# base_board.net
KiCad netlist of a schematic drawn in EAGLE
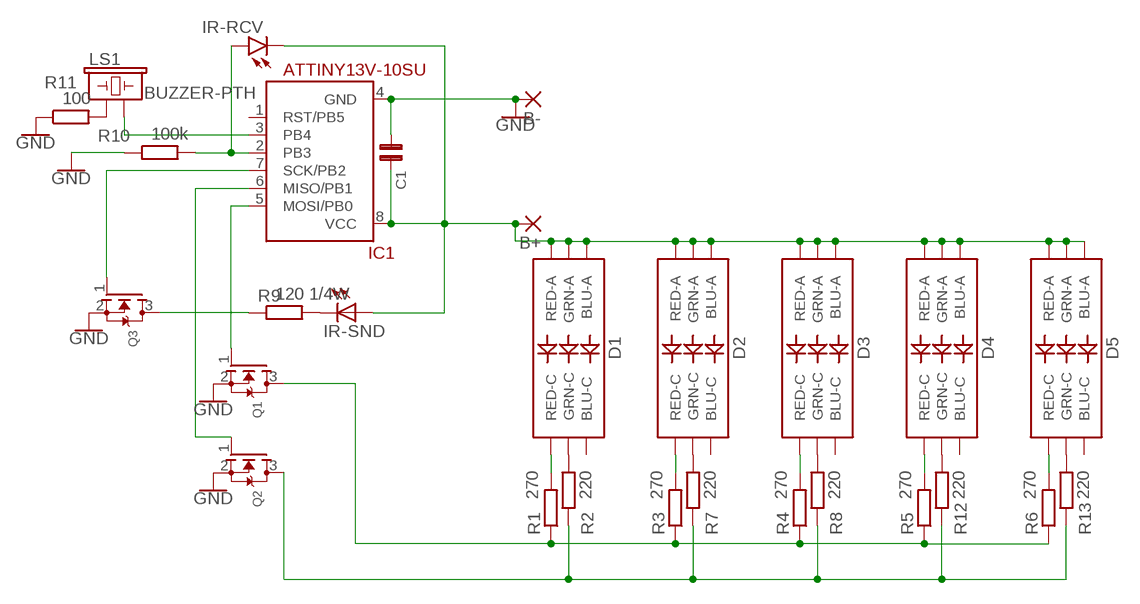
[diagram p0: schematic, sheet 1]

(export (version "E")
  (design (tool "Eeschema 10.0.6"))
  (components
    (comp (ref "B+")
      (value "2,15/1,0")
      (footprint "eagle-import:2,15_1,0")
      (libsource (lib "eagle-import") (part "2,15/1,0"))
    )
    (comp (ref "B-")
      (value "2,15/1,0")
      (footprint "eagle-import:2,15_1,0")
      (libsource (lib "eagle-import") (part "2,15/1,0"))
    )
    (comp (ref "C1")
      (value "C0805")
      (footprint "eagle-import:0805")
      (libsource (lib "eagle-import") (part "C0805"))
    )
    (comp (ref "D1")
      (value "LED-RGBNO_IC")
      (footprint "eagle-import:LED-TRICOLOR-5050")
      (libsource (lib "eagle-import") (part "LED-RGBNO_IC"))
    )
    (comp (ref "D2")
      (value "LED-RGBNO_IC")
      (footprint "eagle-import:LED-TRICOLOR-5050")
      (libsource (lib "eagle-import") (part "LED-RGBNO_IC"))
    )
    (comp (ref "D3")
      (value "LED-RGBNO_IC")
      (footprint "eagle-import:LED-TRICOLOR-5050")
      (libsource (lib "eagle-import") (part "LED-RGBNO_IC"))
    )
    (comp (ref "D4")
      (value "LED-RGBNO_IC")
      (footprint "eagle-import:LED-TRICOLOR-5050")
      (libsource (lib "eagle-import") (part "LED-RGBNO_IC"))
    )
    (comp (ref "D5")
      (value "LED-RGBNO_IC")
      (footprint "eagle-import:LED-TRICOLOR-5050")
      (libsource (lib "eagle-import") (part "LED-RGBNO_IC"))
    )
    (comp (ref "IC1")
      (value "ATTINY13V-10SU")
      (footprint "eagle-import:SOIC8")
      (libsource (lib "eagle-import") (part "ATTINY13V-10SU"))
    )
    (comp (ref "IR-RCV")
      (value "LED_INPUT")
      (footprint "eagle-import:LED3MM")
      (libsource (lib "eagle-import") (part "LED_INPUT"))
    )
    (comp (ref "IR-SND")
      (value "LED3MM")
      (footprint "eagle-import:LED3MM")
      (libsource (lib "eagle-import") (part "LED3MM"))
    )
    (comp (ref "LS1")
      (value "BUZZER-PTH")
      (footprint "eagle-import:BUZZER-12MM")
      (libsource (lib "eagle-import") (part "BUZZER-PTH"))
    )
    (comp (ref "Q1")
      (value "MOSFET-NREFLOW")
      (footprint "eagle-import:SOT23")
      (libsource (lib "eagle-import") (part "MOSFET-NREFLOW"))
    )
    (comp (ref "Q2")
      (value "MOSFET-NREFLOW")
      (footprint "eagle-import:SOT23")
      (libsource (lib "eagle-import") (part "MOSFET-NREFLOW"))
    )
    (comp (ref "Q3")
      (value "MOSFET-NREFLOW")
      (footprint "eagle-import:SOT23")
      (libsource (lib "eagle-import") (part "MOSFET-NREFLOW"))
    )
    (comp (ref "R1")
      (value "270")
      (footprint "eagle-import:R2012")
      (libsource (lib "eagle-import") (part "R-EU_R2012"))
    )
    (comp (ref "R2")
      (value "220")
      (footprint "eagle-import:R2012")
      (libsource (lib "eagle-import") (part "R-EU_R2012"))
    )
    (comp (ref "R3")
      (value "270")
      (footprint "eagle-import:R2012")
      (libsource (lib "eagle-import") (part "R-EU_R2012"))
    )
    (comp (ref "R4")
      (value "270")
      (footprint "eagle-import:R2012")
      (libsource (lib "eagle-import") (part "R-EU_R2012"))
    )
    (comp (ref "R5")
      (value "270")
      (footprint "eagle-import:R2012")
      (libsource (lib "eagle-import") (part "R-EU_R2012"))
    )
    (comp (ref "R6")
      (value "270")
      (footprint "eagle-import:R2012")
      (libsource (lib "eagle-import") (part "R-EU_R2012"))
    )
    (comp (ref "R7")
      (value "220")
      (footprint "eagle-import:R2012")
      (libsource (lib "eagle-import") (part "R-EU_R2012"))
    )
    (comp (ref "R8")
      (value "220")
      (footprint "eagle-import:R2012")
      (libsource (lib "eagle-import") (part "R-EU_R2012"))
    )
    (comp (ref "R9")
      (value "120 1/4W")
      (footprint "eagle-import:R2012")
      (libsource (lib "eagle-import") (part "R-EU_R2012"))
    )
    (comp (ref "R10")
      (value "100k")
      (footprint "eagle-import:R2012")
      (libsource (lib "eagle-import") (part "R-EU_R2012"))
    )
    (comp (ref "R11")
      (value "100")
      (footprint "eagle-import:R2012")
      (libsource (lib "eagle-import") (part "R-EU_R2012"))
    )
    (comp (ref "R12")
      (value "220")
      (footprint "eagle-import:R2012")
      (libsource (lib "eagle-import") (part "R-EU_R2012"))
    )
    (comp (ref "R13")
      (value "220")
      (footprint "eagle-import:R2012")
      (libsource (lib "eagle-import") (part "R-EU_R2012"))
    )
  )
  (nets
    (net (code "1") (name "GND") (class "Default")
      (node (ref "B-") (pin "1") (pinfunction "P_1") (pintype "passive"))
      (node (ref "C1") (pin "1") (pinfunction "1_1") (pintype "passive"))
      (node (ref "IC1") (pin "4") (pinfunction "GND_4") (pintype "power_in"))
      (node (ref "Q1") (pin "2") (pinfunction "S_2") (pintype "bidirectional"))
      (node (ref "Q2") (pin "2") (pinfunction "S_2") (pintype "bidirectional"))
      (node (ref "Q3") (pin "2") (pinfunction "S_2") (pintype "bidirectional"))
      (node (ref "R10") (pin "1") (pinfunction "1_1") (pintype "passive"))
      (node (ref "R11") (pin "1") (pinfunction "1_1") (pintype "passive"))
    )
    (net (code "2") (name "Net-(B+-P)") (class "Default")
      (node (ref "B+") (pin "1") (pinfunction "P_1") (pintype "passive"))
      (node (ref "C1") (pin "2") (pinfunction "2_2") (pintype "passive"))
      (node (ref "D1") (pin "1") (pinfunction "GRN-A_1") (pintype "bidirectional"))
      (node (ref "D1") (pin "2") (pinfunction "RED-A_2") (pintype "bidirectional"))
      (node (ref "D1") (pin "3") (pinfunction "BLU-A_3") (pintype "bidirectional"))
      (node (ref "D2") (pin "1") (pinfunction "GRN-A_1") (pintype "bidirectional"))
      (node (ref "D2") (pin "2") (pinfunction "RED-A_2") (pintype "bidirectional"))
      (node (ref "D2") (pin "3") (pinfunction "BLU-A_3") (pintype "bidirectional"))
      (node (ref "D3") (pin "1") (pinfunction "GRN-A_1") (pintype "bidirectional"))
      (node (ref "D3") (pin "2") (pinfunction "RED-A_2") (pintype "bidirectional"))
      (node (ref "D3") (pin "3") (pinfunction "BLU-A_3") (pintype "bidirectional"))
      (node (ref "D4") (pin "1") (pinfunction "GRN-A_1") (pintype "bidirectional"))
      (node (ref "D4") (pin "2") (pinfunction "RED-A_2") (pintype "bidirectional"))
      (node (ref "D4") (pin "3") (pinfunction "BLU-A_3") (pintype "bidirectional"))
      (node (ref "D5") (pin "1") (pinfunction "GRN-A_1") (pintype "bidirectional"))
      (node (ref "D5") (pin "2") (pinfunction "RED-A_2") (pintype "bidirectional"))
      (node (ref "D5") (pin "3") (pinfunction "BLU-A_3") (pintype "bidirectional"))
      (node (ref "IC1") (pin "8") (pinfunction "VCC_8") (pintype "power_in"))
      (node (ref "IR-RCV") (pin "K") (pinfunction "C_K") (pintype "passive"))
      (node (ref "IR-SND") (pin "A") (pinfunction "A_A") (pintype "passive"))
    )
    (net (code "3") (name "Net-(D1-GRN-C)") (class "Default")
      (node (ref "D1") (pin "6") (pinfunction "GRN-C_6") (pintype "bidirectional"))
      (node (ref "R2") (pin "2") (pinfunction "2_2") (pintype "passive"))
    )
    (net (code "4") (name "Net-(D1-RED-C)") (class "Default")
      (node (ref "D1") (pin "5") (pinfunction "RED-C_5") (pintype "bidirectional"))
      (node (ref "R1") (pin "2") (pinfunction "2_2") (pintype "passive"))
    )
    (net (code "5") (name "Net-(D2-GRN-C)") (class "Default")
      (node (ref "D2") (pin "6") (pinfunction "GRN-C_6") (pintype "bidirectional"))
      (node (ref "R7") (pin "2") (pinfunction "2_2") (pintype "passive"))
    )
    (net (code "6") (name "Net-(D2-RED-C)") (class "Default")
      (node (ref "D2") (pin "5") (pinfunction "RED-C_5") (pintype "bidirectional"))
      (node (ref "R3") (pin "2") (pinfunction "2_2") (pintype "passive"))
    )
    (net (code "7") (name "Net-(D3-GRN-C)") (class "Default")
      (node (ref "D3") (pin "6") (pinfunction "GRN-C_6") (pintype "bidirectional"))
      (node (ref "R8") (pin "2") (pinfunction "2_2") (pintype "passive"))
    )
    (net (code "8") (name "Net-(D3-RED-C)") (class "Default")
      (node (ref "D3") (pin "5") (pinfunction "RED-C_5") (pintype "bidirectional"))
      (node (ref "R4") (pin "2") (pinfunction "2_2") (pintype "passive"))
    )
    (net (code "9") (name "Net-(D4-GRN-C)") (class "Default")
      (node (ref "D4") (pin "6") (pinfunction "GRN-C_6") (pintype "bidirectional"))
      (node (ref "R12") (pin "2") (pinfunction "2_2") (pintype "passive"))
    )
    (net (code "10") (name "Net-(D4-RED-C)") (class "Default")
      (node (ref "D4") (pin "5") (pinfunction "RED-C_5") (pintype "bidirectional"))
      (node (ref "R5") (pin "2") (pinfunction "2_2") (pintype "passive"))
    )
    (net (code "11") (name "Net-(D5-GRN-C)") (class "Default")
      (node (ref "D5") (pin "6") (pinfunction "GRN-C_6") (pintype "bidirectional"))
      (node (ref "R13") (pin "2") (pinfunction "2_2") (pintype "passive"))
    )
    (net (code "12") (name "Net-(D5-RED-C)") (class "Default")
      (node (ref "D5") (pin "5") (pinfunction "RED-C_5") (pintype "bidirectional"))
      (node (ref "R6") (pin "2") (pinfunction "2_2") (pintype "passive"))
    )
    (net (code "13") (name "Net-(IC1-MISO{slash}PB1)") (class "Default")
      (node (ref "IC1") (pin "6") (pinfunction "MISO/PB1_6") (pintype "bidirectional"))
      (node (ref "Q2") (pin "1") (pinfunction "G_1") (pintype "bidirectional"))
    )
    (net (code "14") (name "Net-(IC1-MOSI{slash}PB0)") (class "Default")
      (node (ref "IC1") (pin "5") (pinfunction "MOSI/PB0_5") (pintype "bidirectional"))
      (node (ref "Q1") (pin "1") (pinfunction "G_1") (pintype "bidirectional"))
    )
    (net (code "15") (name "Net-(IC1-PB3)") (class "Default")
      (node (ref "IC1") (pin "2") (pinfunction "PB3_2") (pintype "bidirectional"))
      (node (ref "IR-RCV") (pin "A") (pinfunction "A_A") (pintype "passive"))
      (node (ref "R10") (pin "2") (pinfunction "2_2") (pintype "passive"))
    )
    (net (code "16") (name "Net-(IC1-PB4)") (class "Default")
      (node (ref "IC1") (pin "3") (pinfunction "PB4_3") (pintype "bidirectional"))
      (node (ref "LS1") (pin "-") (pinfunction "2_-") (pintype "passive"))
    )
    (net (code "17") (name "Net-(IC1-SCK{slash}PB2)") (class "Default")
      (node (ref "IC1") (pin "7") (pinfunction "SCK/PB2_7") (pintype "bidirectional"))
      (node (ref "Q3") (pin "1") (pinfunction "G_1") (pintype "bidirectional"))
    )
    (net (code "18") (name "Net-(IR-SND-C)") (class "Default")
      (node (ref "IR-SND") (pin "K") (pinfunction "C_K") (pintype "passive"))
      (node (ref "R9") (pin "2") (pinfunction "2_2") (pintype "passive"))
    )
    (net (code "19") (name "Net-(LS1-1)") (class "Default")
      (node (ref "LS1") (pin "+") (pinfunction "1_+") (pintype "passive"))
      (node (ref "R11") (pin "2") (pinfunction "2_2") (pintype "passive"))
    )
    (net (code "20") (name "Net-(Q1-D)") (class "Default")
      (node (ref "Q1") (pin "3") (pinfunction "D_3") (pintype "bidirectional"))
      (node (ref "R1") (pin "1") (pinfunction "1_1") (pintype "passive"))
      (node (ref "R3") (pin "1") (pinfunction "1_1") (pintype "passive"))
      (node (ref "R4") (pin "1") (pinfunction "1_1") (pintype "passive"))
      (node (ref "R5") (pin "1") (pinfunction "1_1") (pintype "passive"))
      (node (ref "R6") (pin "1") (pinfunction "1_1") (pintype "passive"))
    )
    (net (code "21") (name "Net-(Q2-D)") (class "Default")
      (node (ref "Q2") (pin "3") (pinfunction "D_3") (pintype "bidirectional"))
      (node (ref "R12") (pin "1") (pinfunction "1_1") (pintype "passive"))
      (node (ref "R13") (pin "1") (pinfunction "1_1") (pintype "passive"))
      (node (ref "R2") (pin "1") (pinfunction "1_1") (pintype "passive"))
      (node (ref "R7") (pin "1") (pinfunction "1_1") (pintype "passive"))
      (node (ref "R8") (pin "1") (pinfunction "1_1") (pintype "passive"))
    )
    (net (code "22") (name "Net-(Q3-D)") (class "Default")
      (node (ref "Q3") (pin "3") (pinfunction "D_3") (pintype "bidirectional"))
      (node (ref "R9") (pin "1") (pinfunction "1_1") (pintype "passive"))
    )
    (net (code "23") (name "unconnected-(D1-BLU-C-Pad4)") (class "Default")
      (node (ref "D1") (pin "4") (pinfunction "BLU-C_4") (pintype "bidirectional"))
    )
    (net (code "24") (name "unconnected-(D2-BLU-C-Pad4)") (class "Default")
      (node (ref "D2") (pin "4") (pinfunction "BLU-C_4") (pintype "bidirectional"))
    )
    (net (code "25") (name "unconnected-(D3-BLU-C-Pad4)") (class "Default")
      (node (ref "D3") (pin "4") (pinfunction "BLU-C_4") (pintype "bidirectional"))
    )
    (net (code "26") (name "unconnected-(D4-BLU-C-Pad4)") (class "Default")
      (node (ref "D4") (pin "4") (pinfunction "BLU-C_4") (pintype "bidirectional"))
    )
    (net (code "27") (name "unconnected-(D5-BLU-C-Pad4)") (class "Default")
      (node (ref "D5") (pin "4") (pinfunction "BLU-C_4") (pintype "bidirectional"))
    )
    (net (code "28") (name "unconnected-(IC1-RST{slash}PB5-Pad1)") (class "Default")
      (node (ref "IC1") (pin "1") (pinfunction "RST/PB5_1") (pintype "bidirectional"))
    )
  )
)
